# shield_v4.net
KiCad netlist of a schematic drawn in EAGLE
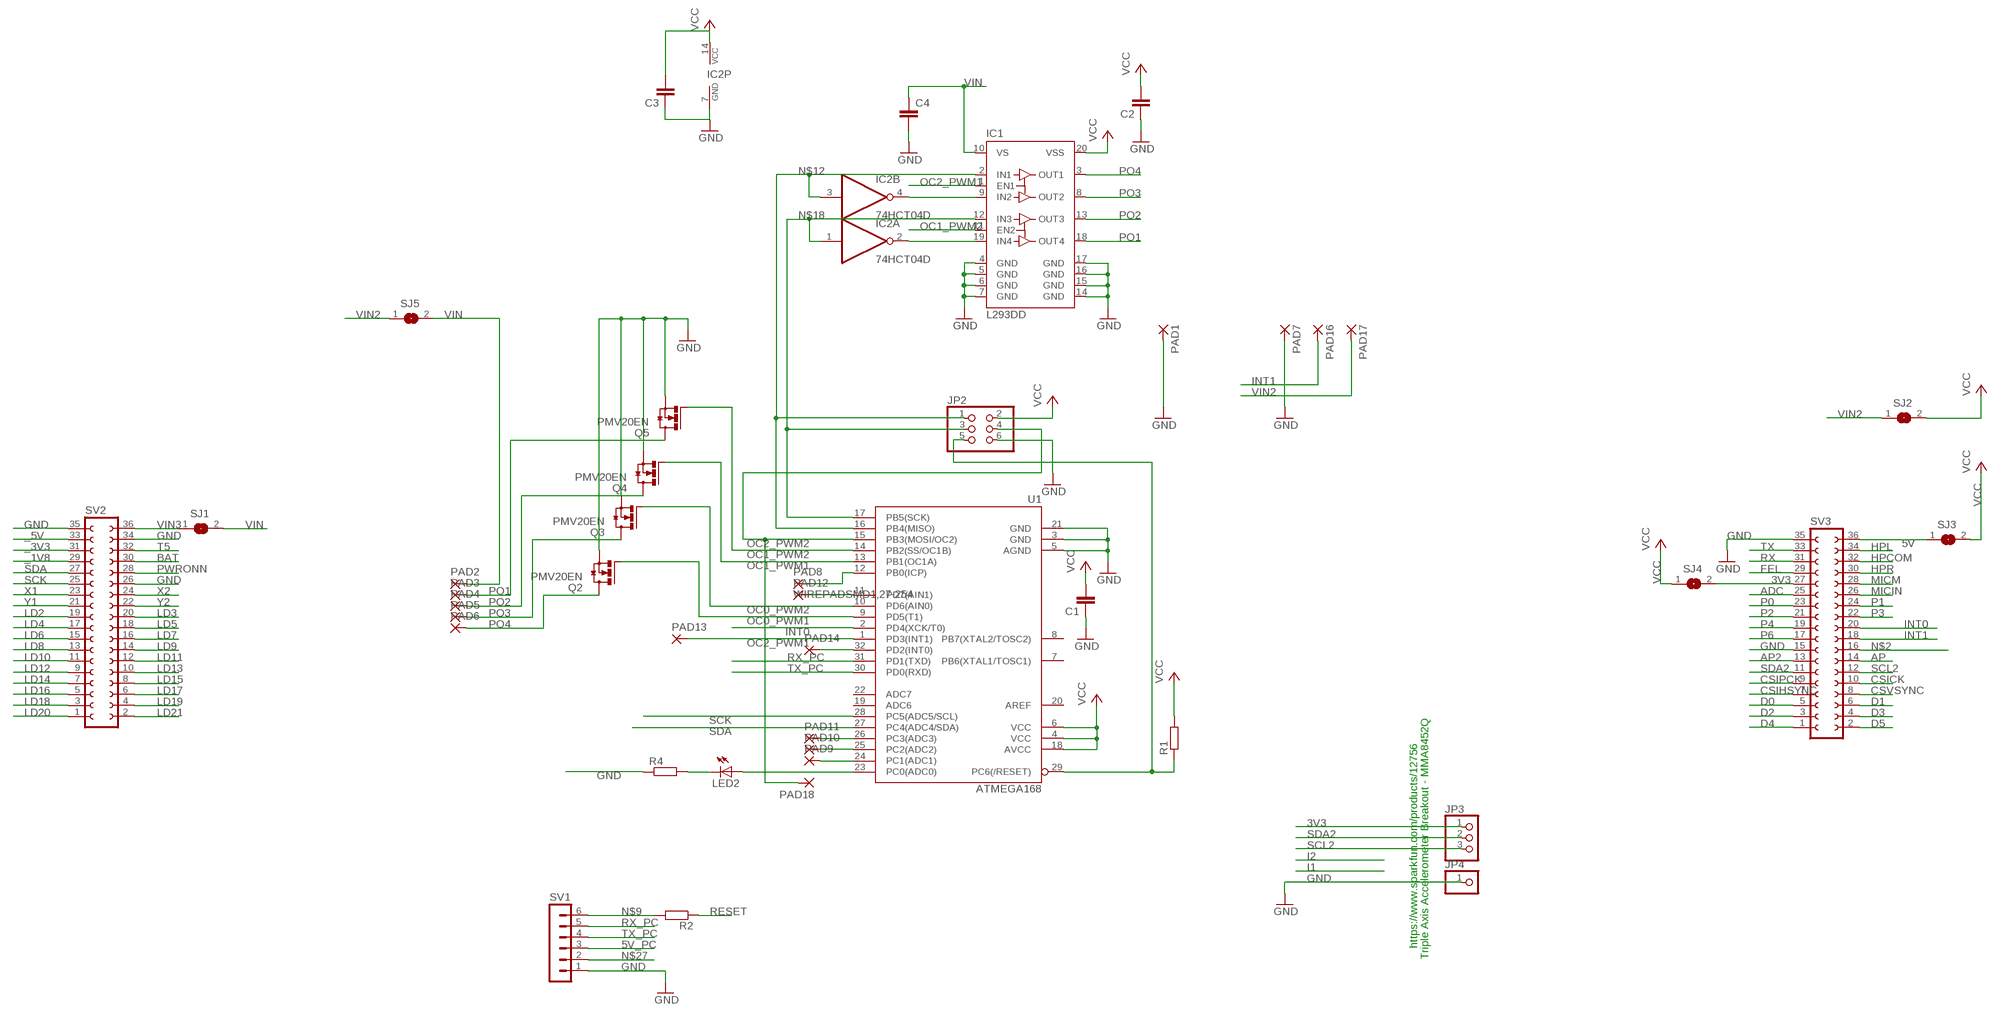
[diagram p0: schematic, sheet 1]

(export (version "E")
  (design (tool "Eeschema 10.0.6"))
  (components
    (comp (ref "C1")
      (value "C-EUC0805")
      (footprint "eagle-import:C0805")
      (libsource (lib "eagle-import") (part "C-EUC0805"))
    )
    (comp (ref "C2")
      (value "C-EUC0805")
      (footprint "eagle-import:C0805")
      (libsource (lib "eagle-import") (part "C-EUC0805"))
    )
    (comp (ref "C3")
      (value "C-EUC0805")
      (footprint "eagle-import:C0805")
      (libsource (lib "eagle-import") (part "C-EUC0805"))
    )
    (comp (ref "C4")
      (value "C-EUC1210")
      (footprint "eagle-import:C1210")
      (libsource (lib "eagle-import") (part "C-EUC1210"))
    )
    (comp (ref "IC1")
      (value "L293DD")
      (footprint "eagle-import:SO20")
      (libsource (lib "eagle-import") (part "L293DD"))
    )
    (comp (ref "IC2")
      (value "74HCT04D")
      (footprint "eagle-import:SO14")
      (libsource (lib "eagle-import") (part "7404DHCT"))
    )
    (comp (ref "JP2")
      (value "PINHD-2X3")
      (footprint "eagle-import:2X03")
      (libsource (lib "eagle-import") (part "PINHD-2X3"))
    )
    (comp (ref "JP3")
      (value "PINHD-1X3")
      (footprint "eagle-import:1X03")
      (libsource (lib "eagle-import") (part "PINHD-1X3"))
    )
    (comp (ref "JP4")
      (value "PINHD-1X1")
      (footprint "eagle-import:1X01")
      (libsource (lib "eagle-import") (part "PINHD-1X1"))
    )
    (comp (ref "LED2")
      (value "LEDCHIP-LED0805")
      (footprint "eagle-import:CHIP-LED0805")
      (libsource (lib "eagle-import") (part "LEDCHIP-LED0805"))
    )
    (comp (ref "PAD1")
      (value "3,17/1,3")
      (footprint "eagle-import:3,17_1,3")
      (libsource (lib "eagle-import") (part "3,17/1,3"))
    )
    (comp (ref "PAD2")
      (value "3,17/1,3")
      (footprint "eagle-import:3,17_1,3")
      (libsource (lib "eagle-import") (part "3,17/1,3"))
    )
    (comp (ref "PAD3")
      (value "3,17/1,3")
      (footprint "eagle-import:3,17_1,3")
      (libsource (lib "eagle-import") (part "3,17/1,3"))
    )
    (comp (ref "PAD4")
      (value "3,17/1,3")
      (footprint "eagle-import:3,17_1,3")
      (libsource (lib "eagle-import") (part "3,17/1,3"))
    )
    (comp (ref "PAD5")
      (value "3,17/1,3")
      (footprint "eagle-import:3,17_1,3")
      (libsource (lib "eagle-import") (part "3,17/1,3"))
    )
    (comp (ref "PAD6")
      (value "3,17/1,3")
      (footprint "eagle-import:3,17_1,3")
      (libsource (lib "eagle-import") (part "3,17/1,3"))
    )
    (comp (ref "PAD7")
      (value "3,17/1,3")
      (footprint "eagle-import:3,17_1,3")
      (libsource (lib "eagle-import") (part "3,17/1,3"))
    )
    (comp (ref "PAD8")
      (value "WIREPADSMD1,27-254")
      (footprint "eagle-import:SMD1,27-2,54")
      (libsource (lib "eagle-import") (part "WIREPADSMD1,27-254"))
    )
    (comp (ref "PAD9")
      (value "3,17/1,3")
      (footprint "eagle-import:3,17_1,3")
      (libsource (lib "eagle-import") (part "3,17/1,3"))
    )
    (comp (ref "PAD10")
      (value "3,17/1,3")
      (footprint "eagle-import:3,17_1,3")
      (libsource (lib "eagle-import") (part "3,17/1,3"))
    )
    (comp (ref "PAD11")
      (value "3,17/1,3")
      (footprint "eagle-import:3,17_1,3")
      (libsource (lib "eagle-import") (part "3,17/1,3"))
    )
    (comp (ref "PAD12")
      (value "SMD2")
      (footprint "eagle-import:SMD1,27-2,54")
      (libsource (lib "eagle-import") (part "SMD2"))
    )
    (comp (ref "PAD13")
      (value "SMD2")
      (footprint "eagle-import:SMD1,27-2,54")
      (libsource (lib "eagle-import") (part "SMD2"))
    )
    (comp (ref "PAD14")
      (value "3,17/1,3")
      (footprint "eagle-import:3,17_1,3")
      (libsource (lib "eagle-import") (part "3,17/1,3"))
    )
    (comp (ref "PAD16")
      (value "3,17/1,3")
      (footprint "eagle-import:3,17_1,3")
      (libsource (lib "eagle-import") (part "3,17/1,3"))
    )
    (comp (ref "PAD17")
      (value "3,17/1,3")
      (footprint "eagle-import:3,17_1,3")
      (libsource (lib "eagle-import") (part "3,17/1,3"))
    )
    (comp (ref "PAD18")
      (value "3,17/1,3")
      (footprint "eagle-import:3,17_1,3")
      (libsource (lib "eagle-import") (part "3,17/1,3"))
    )
    (comp (ref "Q2")
      (value "PMV20EN")
      (footprint "eagle-import:SOT223")
      (libsource (lib "eagle-import") (part "NMOSFET_SMD_223"))
    )
    (comp (ref "Q3")
      (value "PMV20EN")
      (footprint "eagle-import:SOT223")
      (libsource (lib "eagle-import") (part "NMOSFET_SMD_223"))
    )
    (comp (ref "Q4")
      (value "PMV20EN")
      (footprint "eagle-import:SOT223")
      (libsource (lib "eagle-import") (part "NMOSFET_SMD_223"))
    )
    (comp (ref "Q5")
      (value "PMV20EN")
      (footprint "eagle-import:SOT223")
      (libsource (lib "eagle-import") (part "NMOSFET_SMD_223"))
    )
    (comp (ref "R1")
      (value "R-EU_M1206")
      (footprint "eagle-import:M1206")
      (libsource (lib "eagle-import") (part "R-EU_M1206"))
    )
    (comp (ref "R2")
      (value "R-EU_M1206")
      (footprint "eagle-import:M1206")
      (libsource (lib "eagle-import") (part "R-EU_M1206"))
    )
    (comp (ref "R4")
      (value "R-EU_M1206")
      (footprint "eagle-import:M1206")
      (libsource (lib "eagle-import") (part "R-EU_M1206"))
    )
    (comp (ref "SJ1") (value "SJ") (footprint "eagle-import:SJ") (libsource (lib "eagle-import") (part "SJ")))
    (comp (ref "SJ2") (value "SJ") (footprint "eagle-import:SJ") (libsource (lib "eagle-import") (part "SJ")))
    (comp (ref "SJ3") (value "SJ") (footprint "eagle-import:SJ") (libsource (lib "eagle-import") (part "SJ")))
    (comp (ref "SJ4") (value "SJ") (footprint "eagle-import:SJ") (libsource (lib "eagle-import") (part "SJ")))
    (comp (ref "SJ5") (value "SJ") (footprint "eagle-import:SJ") (libsource (lib "eagle-import") (part "SJ")))
    (comp (ref "SV1")
      (value "MA06-1")
      (footprint "eagle-import:MA06-1")
      (libsource (lib "eagle-import") (part "MA06-1"))
    )
    (comp (ref "SV2")
      (value "FE18-2")
      (footprint "eagle-import:FE18-2")
      (libsource (lib "eagle-import") (part "FE18-2"))
    )
    (comp (ref "SV3")
      (value "FE18-2")
      (footprint "eagle-import:FE18-2")
      (libsource (lib "eagle-import") (part "FE18-2"))
    )
    (comp (ref "U1")
      (value "ATMEGA168")
      (footprint "eagle-import:TQFP32-08")
      (libsource (lib "eagle-import") (part "ATMEGA168"))
    )
  )
  (nets
    (net (code "1") (name "/3V3") (class "Default")
      (node (ref "JP3") (pin "1") (pinfunction "1_1") (pintype "passive"))
      (node (ref "SJ4") (pin "2") (pinfunction "2_2") (pintype "passive"))
      (node (ref "SV3") (pin "27") (pinfunction "27_27") (pintype "passive"))
    )
    (net (code "2") (name "/5V") (class "Default")
      (node (ref "SJ3") (pin "1") (pinfunction "1_1") (pintype "passive"))
      (node (ref "SV3") (pin "36") (pinfunction "36_36") (pintype "passive"))
    )
    (net (code "3") (name "/5V_PC") (class "Default")
      (node (ref "SV1") (pin "3") (pinfunction "3_3") (pintype "passive"))
    )
    (net (code "4") (name "/ADC") (class "Default")
      (node (ref "SV3") (pin "25") (pinfunction "25_25") (pintype "passive"))
    )
    (net (code "5") (name "/AP") (class "Default")
      (node (ref "SV3") (pin "14") (pinfunction "14_14") (pintype "passive"))
    )
    (net (code "6") (name "/AP2") (class "Default")
      (node (ref "SV3") (pin "13") (pinfunction "13_13") (pintype "passive"))
    )
    (net (code "7") (name "/BAT") (class "Default")
      (node (ref "SV2") (pin "30") (pinfunction "30_30") (pintype "passive"))
    )
    (net (code "8") (name "/CSICK") (class "Default")
      (node (ref "SV3") (pin "10") (pinfunction "10_10") (pintype "passive"))
    )
    (net (code "9") (name "/CSIHSYNC") (class "Default")
      (node (ref "SV3") (pin "7") (pinfunction "7_7") (pintype "passive"))
    )
    (net (code "10") (name "/CSIPCK") (class "Default")
      (node (ref "SV3") (pin "9") (pinfunction "9_9") (pintype "passive"))
    )
    (net (code "11") (name "/CSVSYNC") (class "Default")
      (node (ref "SV3") (pin "8") (pinfunction "8_8") (pintype "passive"))
    )
    (net (code "12") (name "/D0") (class "Default")
      (node (ref "SV3") (pin "5") (pinfunction "5_5") (pintype "passive"))
    )
    (net (code "13") (name "/D1") (class "Default")
      (node (ref "SV3") (pin "6") (pinfunction "6_6") (pintype "passive"))
    )
    (net (code "14") (name "/D2") (class "Default")
      (node (ref "SV3") (pin "3") (pinfunction "3_3") (pintype "passive"))
    )
    (net (code "15") (name "/D3") (class "Default")
      (node (ref "SV3") (pin "4") (pinfunction "4_4") (pintype "passive"))
    )
    (net (code "16") (name "/D4") (class "Default")
      (node (ref "SV3") (pin "1") (pinfunction "1_1") (pintype "passive"))
    )
    (net (code "17") (name "/D5") (class "Default")
      (node (ref "SV3") (pin "2") (pinfunction "2_2") (pintype "passive"))
    )
    (net (code "18") (name "/FEL") (class "Default")
      (node (ref "SV3") (pin "29") (pinfunction "29_29") (pintype "passive"))
    )
    (net (code "19") (name "/HPCOM") (class "Default")
      (node (ref "SV3") (pin "32") (pinfunction "32_32") (pintype "passive"))
    )
    (net (code "20") (name "/HPL") (class "Default")
      (node (ref "SV3") (pin "34") (pinfunction "34_34") (pintype "passive"))
    )
    (net (code "21") (name "/HPR") (class "Default")
      (node (ref "SV3") (pin "30") (pinfunction "30_30") (pintype "passive"))
    )
    (net (code "24") (name "/INT0") (class "Default")
      (node (ref "SV3") (pin "20") (pinfunction "20_20") (pintype "passive"))
      (node (ref "U1") (pin "2") (pinfunction "PD4(XCK/T0)_2") (pintype "bidirectional"))
    )
    (net (code "25") (name "/INT1") (class "Default")
      (node (ref "PAD16") (pin "1") (pinfunction "P_1") (pintype "passive"))
      (node (ref "SV3") (pin "18") (pinfunction "18_18") (pintype "passive"))
    )
    (net (code "26") (name "/LD2") (class "Default")
      (node (ref "SV2") (pin "19") (pinfunction "19_19") (pintype "passive"))
    )
    (net (code "27") (name "/LD3") (class "Default")
      (node (ref "SV2") (pin "20") (pinfunction "20_20") (pintype "passive"))
    )
    (net (code "28") (name "/LD4") (class "Default")
      (node (ref "SV2") (pin "17") (pinfunction "17_17") (pintype "passive"))
    )
    (net (code "29") (name "/LD5") (class "Default")
      (node (ref "SV2") (pin "18") (pinfunction "18_18") (pintype "passive"))
    )
    (net (code "30") (name "/LD6") (class "Default")
      (node (ref "SV2") (pin "15") (pinfunction "15_15") (pintype "passive"))
    )
    (net (code "31") (name "/LD7") (class "Default")
      (node (ref "SV2") (pin "16") (pinfunction "16_16") (pintype "passive"))
    )
    (net (code "32") (name "/LD8") (class "Default")
      (node (ref "SV2") (pin "13") (pinfunction "13_13") (pintype "passive"))
    )
    (net (code "33") (name "/LD9") (class "Default")
      (node (ref "SV2") (pin "14") (pinfunction "14_14") (pintype "passive"))
    )
    (net (code "34") (name "/LD10") (class "Default")
      (node (ref "SV2") (pin "11") (pinfunction "11_11") (pintype "passive"))
    )
    (net (code "35") (name "/LD11") (class "Default")
      (node (ref "SV2") (pin "12") (pinfunction "12_12") (pintype "passive"))
    )
    (net (code "36") (name "/LD12") (class "Default")
      (node (ref "SV2") (pin "9") (pinfunction "9_9") (pintype "passive"))
    )
    (net (code "37") (name "/LD13") (class "Default")
      (node (ref "SV2") (pin "10") (pinfunction "10_10") (pintype "passive"))
    )
    (net (code "38") (name "/LD14") (class "Default")
      (node (ref "SV2") (pin "7") (pinfunction "7_7") (pintype "passive"))
    )
    (net (code "39") (name "/LD15") (class "Default")
      (node (ref "SV2") (pin "8") (pinfunction "8_8") (pintype "passive"))
    )
    (net (code "40") (name "/LD16") (class "Default")
      (node (ref "SV2") (pin "5") (pinfunction "5_5") (pintype "passive"))
    )
    (net (code "41") (name "/LD17") (class "Default")
      (node (ref "SV2") (pin "6") (pinfunction "6_6") (pintype "passive"))
    )
    (net (code "42") (name "/LD18") (class "Default")
      (node (ref "SV2") (pin "3") (pinfunction "3_3") (pintype "passive"))
    )
    (net (code "43") (name "/LD19") (class "Default")
      (node (ref "SV2") (pin "4") (pinfunction "4_4") (pintype "passive"))
    )
    (net (code "44") (name "/LD20") (class "Default")
      (node (ref "SV2") (pin "1") (pinfunction "1_1") (pintype "passive"))
    )
    (net (code "45") (name "/LD21") (class "Default")
      (node (ref "SV2") (pin "2") (pinfunction "2_2") (pintype "passive"))
    )
    (net (code "46") (name "/MICIN") (class "Default")
      (node (ref "SV3") (pin "26") (pinfunction "26_26") (pintype "passive"))
    )
    (net (code "47") (name "/MICM") (class "Default")
      (node (ref "SV3") (pin "28") (pinfunction "28_28") (pintype "passive"))
    )
    (net (code "48") (name "/N$2") (class "Default")
      (node (ref "SV3") (pin "16") (pinfunction "16_16") (pintype "passive"))
    )
    (net (code "49") (name "/N$9") (class "Default")
      (node (ref "R2") (pin "2") (pinfunction "2_2") (pintype "passive"))
      (node (ref "SV1") (pin "6") (pinfunction "6_6") (pintype "passive"))
    )
    (net (code "50") (name "/N$12") (class "Default")
      (node (ref "IC1") (pin "2") (pinfunction "IN1_2") (pintype "input"))
      (node (ref "IC2") (pin "3") (pinfunction "I_3") (pintype "input"))
      (node (ref "JP2") (pin "1") (pinfunction "1_1") (pintype "passive"))
      (node (ref "U1") (pin "16") (pinfunction "PB4(MISO)_16") (pintype "bidirectional"))
    )
    (net (code "51") (name "/N$18") (class "Default")
      (node (ref "IC1") (pin "12") (pinfunction "IN3_12") (pintype "input"))
      (node (ref "IC2") (pin "1") (pinfunction "I_1") (pintype "input"))
      (node (ref "JP2") (pin "3") (pinfunction "3_3") (pintype "passive"))
      (node (ref "U1") (pin "17") (pinfunction "PB5(SCK)_17") (pintype "bidirectional"))
    )
    (net (code "52") (name "/N$27") (class "Default")
      (node (ref "SV1") (pin "2") (pinfunction "2_2") (pintype "passive"))
    )
    (net (code "53") (name "/OC0_PWM1") (class "Default")
      (node (ref "Q2") (pin "1") (pinfunction "G_1") (pintype "passive"))
      (node (ref "U1") (pin "9") (pinfunction "PD5(T1)_9") (pintype "bidirectional"))
    )
    (net (code "54") (name "/OC0_PWM2") (class "Default")
      (node (ref "Q3") (pin "1") (pinfunction "G_1") (pintype "passive"))
      (node (ref "U1") (pin "10") (pinfunction "PD6(AIN0)_10") (pintype "bidirectional"))
    )
    (net (code "55") (name "/OC1_PWM1") (class "Default")
      (node (ref "Q4") (pin "1") (pinfunction "G_1") (pintype "passive"))
      (node (ref "U1") (pin "13") (pinfunction "PB1(OC1A)_13") (pintype "bidirectional"))
    )
    (net (code "56") (name "/OC1_PWM2") (class "Default")
      (node (ref "IC1") (pin "11") (pinfunction "EN2_11") (pintype "input"))
      (node (ref "Q5") (pin "1") (pinfunction "G_1") (pintype "passive"))
      (node (ref "U1") (pin "14") (pinfunction "PB2(SS/OC1B)_14") (pintype "bidirectional"))
    )
    (net (code "57") (name "/OC2_PWM1") (class "Default")
      (node (ref "IC1") (pin "1") (pinfunction "EN1_1") (pintype "input"))
      (node (ref "PAD13") (pin "1") (pinfunction "P_1") (pintype "passive"))
      (node (ref "U1") (pin "1") (pinfunction "PD3(INT1)_1") (pintype "bidirectional"))
    )
    (net (code "58") (name "/OC2_PWM2") (class "Default")
      (node (ref "JP2") (pin "4") (pinfunction "4_4") (pintype "passive"))
      (node (ref "PAD18") (pin "1") (pinfunction "P_1") (pintype "passive"))
      (node (ref "U1") (pin "15") (pinfunction "PB3(MOSI/OC2)_15") (pintype "bidirectional"))
    )
    (net (code "59") (name "/P0") (class "Default")
      (node (ref "SV3") (pin "23") (pinfunction "23_23") (pintype "passive"))
    )
    (net (code "60") (name "/P1") (class "Default")
      (node (ref "SV3") (pin "24") (pinfunction "24_24") (pintype "passive"))
    )
    (net (code "61") (name "/P2") (class "Default")
      (node (ref "SV3") (pin "21") (pinfunction "21_21") (pintype "passive"))
    )
    (net (code "62") (name "/P3") (class "Default")
      (node (ref "SV3") (pin "22") (pinfunction "22_22") (pintype "passive"))
    )
    (net (code "63") (name "/P4") (class "Default")
      (node (ref "SV3") (pin "19") (pinfunction "19_19") (pintype "passive"))
    )
    (net (code "64") (name "/P6") (class "Default")
      (node (ref "SV3") (pin "17") (pinfunction "17_17") (pintype "passive"))
    )
    (net (code "65") (name "/PO1") (class "Default")
      (node (ref "IC1") (pin "18") (pinfunction "OUT4_18") (pintype "output"))
      (node (ref "PAD3") (pin "1") (pinfunction "P_1") (pintype "passive"))
      (node (ref "Q5") (pin "2") (pinfunction "D_2") (pintype "passive"))
      (node (ref "Q5") (pin "4") (pinfunction "D_4") (pintype "passive"))
    )
    (net (code "66") (name "/PO2") (class "Default")
      (node (ref "IC1") (pin "13") (pinfunction "OUT3_13") (pintype "output"))
      (node (ref "PAD4") (pin "1") (pinfunction "P_1") (pintype "passive"))
      (node (ref "Q4") (pin "2") (pinfunction "D_2") (pintype "passive"))
      (node (ref "Q4") (pin "4") (pinfunction "D_4") (pintype "passive"))
    )
    (net (code "67") (name "/PO3") (class "Default")
      (node (ref "IC1") (pin "8") (pinfunction "OUT2_8") (pintype "output"))
      (node (ref "PAD5") (pin "1") (pinfunction "P_1") (pintype "passive"))
      (node (ref "Q3") (pin "2") (pinfunction "D_2") (pintype "passive"))
      (node (ref "Q3") (pin "4") (pinfunction "D_4") (pintype "passive"))
    )
    (net (code "68") (name "/PO4") (class "Default")
      (node (ref "IC1") (pin "3") (pinfunction "OUT1_3") (pintype "output"))
      (node (ref "PAD6") (pin "1") (pinfunction "P_1") (pintype "passive"))
      (node (ref "Q2") (pin "2") (pinfunction "D_2") (pintype "passive"))
      (node (ref "Q2") (pin "4") (pinfunction "D_4") (pintype "passive"))
    )
    (net (code "69") (name "/PWRONN") (class "Default")
      (node (ref "SV2") (pin "28") (pinfunction "28_28") (pintype "passive"))
    )
    (net (code "70") (name "/RESET") (class "Default")
      (node (ref "JP2") (pin "5") (pinfunction "5_5") (pintype "passive"))
      (node (ref "R1") (pin "1") (pinfunction "1_1") (pintype "passive"))
      (node (ref "R2") (pin "1") (pinfunction "1_1") (pintype "passive"))
      (node (ref "U1") (pin "29") (pinfunction "PC6(/RESET)_29") (pintype "bidirectional"))
    )
    (net (code "71") (name "/RX") (class "Default")
      (node (ref "SV3") (pin "31") (pinfunction "31_31") (pintype "passive"))
    )
    (net (code "72") (name "/RX_PC") (class "Default")
      (node (ref "SV1") (pin "5") (pinfunction "5_5") (pintype "passive"))
      (node (ref "U1") (pin "31") (pinfunction "PD1(TXD)_31") (pintype "bidirectional"))
    )
    (net (code "73") (name "/SCK") (class "Default")
      (node (ref "SV2") (pin "25") (pinfunction "25_25") (pintype "passive"))
      (node (ref "U1") (pin "28") (pinfunction "PC5(ADC5/SCL)_28") (pintype "bidirectional"))
    )
    (net (code "74") (name "/SCL2") (class "Default")
      (node (ref "JP3") (pin "3") (pinfunction "3_3") (pintype "passive"))
      (node (ref "SV3") (pin "12") (pinfunction "12_12") (pintype "passive"))
    )
    (net (code "75") (name "/SDA") (class "Default")
      (node (ref "SV2") (pin "27") (pinfunction "27_27") (pintype "passive"))
      (node (ref "U1") (pin "27") (pinfunction "PC4(ADC4/SDA)_27") (pintype "bidirectional"))
    )
    (net (code "76") (name "/SDA2") (class "Default")
      (node (ref "JP3") (pin "2") (pinfunction "2_2") (pintype "passive"))
      (node (ref "SV3") (pin "11") (pinfunction "11_11") (pintype "passive"))
    )
    (net (code "77") (name "/T5") (class "Default")
      (node (ref "SV2") (pin "32") (pinfunction "32_32") (pintype "passive"))
    )
    (net (code "78") (name "/TX") (class "Default")
      (node (ref "SV3") (pin "33") (pinfunction "33_33") (pintype "passive"))
    )
    (net (code "79") (name "/TX_PC") (class "Default")
      (node (ref "SV1") (pin "4") (pinfunction "4_4") (pintype "passive"))
      (node (ref "U1") (pin "30") (pinfunction "PD0(RXD)_30") (pintype "bidirectional"))
    )
    (net (code "80") (name "/VIN") (class "Default")
      (node (ref "C4") (pin "1") (pinfunction "1_1") (pintype "passive"))
      (node (ref "IC1") (pin "10") (pinfunction "VS_10") (pintype "power_in"))
      (node (ref "PAD2") (pin "1") (pinfunction "P_1") (pintype "passive"))
      (node (ref "SJ1") (pin "2") (pinfunction "2_2") (pintype "passive"))
      (node (ref "SJ5") (pin "2") (pinfunction "2_2") (pintype "passive"))
    )
    (net (code "81") (name "/VIN2") (class "Default")
      (node (ref "PAD17") (pin "1") (pinfunction "P_1") (pintype "passive"))
      (node (ref "SJ2") (pin "1") (pinfunction "1_1") (pintype "passive"))
      (node (ref "SJ5") (pin "1") (pinfunction "1_1") (pintype "passive"))
    )
    (net (code "82") (name "/VIN3") (class "Default")
      (node (ref "SJ1") (pin "1") (pinfunction "1_1") (pintype "passive"))
      (node (ref "SV2") (pin "36") (pinfunction "36_36") (pintype "passive"))
    )
    (net (code "83") (name "/X1") (class "Default")
      (node (ref "SV2") (pin "23") (pinfunction "23_23") (pintype "passive"))
    )
    (net (code "84") (name "/X2") (class "Default")
      (node (ref "SV2") (pin "24") (pinfunction "24_24") (pintype "passive"))
    )
    (net (code "85") (name "/Y1") (class "Default")
      (node (ref "SV2") (pin "21") (pinfunction "21_21") (pintype "passive"))
    )
    (net (code "86") (name "/Y2") (class "Default")
      (node (ref "SV2") (pin "22") (pinfunction "22_22") (pintype "passive"))
    )
    (net (code "87") (name "/_1V8") (class "Default")
      (node (ref "SV2") (pin "29") (pinfunction "29_29") (pintype "passive"))
    )
    (net (code "88") (name "/_3V3") (class "Default")
      (node (ref "SV2") (pin "31") (pinfunction "31_31") (pintype "passive"))
    )
    (net (code "89") (name "/_5V") (class "Default")
      (node (ref "SV2") (pin "33") (pinfunction "33_33") (pintype "passive"))
    )
    (net (code "90") (name "GND") (class "Default")
      (node (ref "C1") (pin "1") (pinfunction "1_1") (pintype "passive"))
      (node (ref "C2") (pin "1") (pinfunction "1_1") (pintype "passive"))
      (node (ref "C3") (pin "1") (pinfunction "1_1") (pintype "passive"))
      (node (ref "C4") (pin "2") (pinfunction "2_2") (pintype "passive"))
      (node (ref "IC1") (pin "14") (pinfunction "GND_14") (pintype "power_in"))
      (node (ref "IC1") (pin "15") (pinfunction "GND_15") (pintype "power_in"))
      (node (ref "IC1") (pin "16") (pinfunction "GND_16") (pintype "power_in"))
      (node (ref "IC1") (pin "17") (pinfunction "GND_17") (pintype "power_in"))
      (node (ref "IC1") (pin "4") (pinfunction "GND_4") (pintype "power_in"))
      (node (ref "IC1") (pin "5") (pinfunction "GND_5") (pintype "power_in"))
      (node (ref "IC1") (pin "6") (pinfunction "GND_6") (pintype "power_in"))
      (node (ref "IC1") (pin "7") (pinfunction "GND_7") (pintype "power_in"))
      (node (ref "IC2") (pin "7") (pinfunction "GND_7") (pintype "power_in"))
      (node (ref "JP2") (pin "6") (pinfunction "6_6") (pintype "passive"))
      (node (ref "JP4") (pin "1") (pinfunction "1_1") (pintype "passive"))
      (node (ref "PAD1") (pin "1") (pinfunction "P_1") (pintype "passive"))
      (node (ref "PAD7") (pin "1") (pinfunction "P_1") (pintype "passive"))
      (node (ref "Q2") (pin "3") (pinfunction "S_3") (pintype "passive"))
      (node (ref "Q3") (pin "3") (pinfunction "S_3") (pintype "passive"))
      (node (ref "Q4") (pin "3") (pinfunction "S_3") (pintype "passive"))
      (node (ref "Q5") (pin "3") (pinfunction "S_3") (pintype "passive"))
      (node (ref "R4") (pin "1") (pinfunction "1_1") (pintype "passive"))
      (node (ref "SV1") (pin "1") (pinfunction "1_1") (pintype "passive"))
      (node (ref "SV2") (pin "26") (pinfunction "26_26") (pintype "passive"))
      (node (ref "SV2") (pin "34") (pinfunction "34_34") (pintype "passive"))
      (node (ref "SV2") (pin "35") (pinfunction "35_35") (pintype "passive"))
      (node (ref "SV3") (pin "15") (pinfunction "15_15") (pintype "passive"))
      (node (ref "SV3") (pin "35") (pinfunction "35_35") (pintype "passive"))
      (node (ref "U1") (pin "21") (pinfunction "GND_21") (pintype "bidirectional"))
      (node (ref "U1") (pin "3") (pinfunction "GND_3") (pintype "bidirectional"))
      (node (ref "U1") (pin "5") (pinfunction "AGND_5") (pintype "bidirectional"))
    )
    (net (code "91") (name "Net-(IC1-IN2)") (class "Default")
      (node (ref "IC1") (pin "9") (pinfunction "IN2_9") (pintype "input"))
      (node (ref "IC2") (pin "4") (pinfunction "O_4") (pintype "output"))
    )
    (net (code "92") (name "Net-(IC1-IN4)") (class "Default")
      (node (ref "IC1") (pin "19") (pinfunction "IN4_19") (pintype "input"))
      (node (ref "IC2") (pin "2") (pinfunction "O_2") (pintype "output"))
    )
    (net (code "93") (name "Net-(LED2-PadC)") (class "Default")
      (node (ref "LED2") (pin "C") (pinfunction "C_C") (pintype "passive"))
      (node (ref "R4") (pin "2") (pinfunction "2_2") (pintype "passive"))
    )
    (net (code "94") (name "Net-(PAD8-P)") (class "Default")
      (node (ref "PAD8") (pin "1") (pinfunction "P_1") (pintype "passive"))
      (node (ref "U1") (pin "12") (pinfunction "PB0(ICP)_12") (pintype "bidirectional"))
    )
    (net (code "95") (name "Net-(PAD9-P)") (class "Default")
      (node (ref "PAD9") (pin "1") (pinfunction "P_1") (pintype "passive"))
      (node (ref "U1") (pin "24") (pinfunction "PC1(ADC1)_24") (pintype "bidirectional"))
    )
    (net (code "96") (name "Net-(PAD10-P)") (class "Default")
      (node (ref "PAD10") (pin "1") (pinfunction "P_1") (pintype "passive"))
      (node (ref "U1") (pin "25") (pinfunction "PC2(ADC2)_25") (pintype "bidirectional"))
    )
    (net (code "97") (name "Net-(PAD11-P)") (class "Default")
      (node (ref "PAD11") (pin "1") (pinfunction "P_1") (pintype "passive"))
      (node (ref "U1") (pin "26") (pinfunction "PC3(ADC3)_26") (pintype "bidirectional"))
    )
    (net (code "98") (name "Net-(PAD12-P)") (class "Default")
      (node (ref "PAD12") (pin "1") (pinfunction "P_1") (pintype "passive"))
      (node (ref "U1") (pin "11") (pinfunction "PD7(AIN1)_11") (pintype "bidirectional"))
    )
    (net (code "99") (name "Net-(PAD14-P)") (class "Default")
      (node (ref "PAD14") (pin "1") (pinfunction "P_1") (pintype "passive"))
      (node (ref "U1") (pin "32") (pinfunction "PD2(INT0)_32") (pintype "bidirectional"))
    )
    (net (code "100") (name "Net-(U1-PC0(ADC0))") (class "Default")
      (node (ref "LED2") (pin "A") (pinfunction "A_A") (pintype "passive"))
      (node (ref "U1") (pin "23") (pinfunction "PC0(ADC0)_23") (pintype "bidirectional"))
    )
    (net (code "101") (name "VCC") (class "Default")
      (node (ref "C1") (pin "2") (pinfunction "2_2") (pintype "passive"))
      (node (ref "C2") (pin "2") (pinfunction "2_2") (pintype "passive"))
      (node (ref "C3") (pin "2") (pinfunction "2_2") (pintype "passive"))
      (node (ref "IC1") (pin "20") (pinfunction "VSS_20") (pintype "power_in"))
      (node (ref "IC2") (pin "14") (pinfunction "VCC_14") (pintype "power_in"))
      (node (ref "JP2") (pin "2") (pinfunction "2_2") (pintype "passive"))
      (node (ref "R1") (pin "2") (pinfunction "2_2") (pintype "passive"))
      (node (ref "SJ2") (pin "2") (pinfunction "2_2") (pintype "passive"))
      (node (ref "SJ3") (pin "2") (pinfunction "2_2") (pintype "passive"))
      (node (ref "SJ4") (pin "1") (pinfunction "1_1") (pintype "passive"))
      (node (ref "U1") (pin "18") (pinfunction "AVCC_18") (pintype "bidirectional"))
      (node (ref "U1") (pin "4") (pinfunction "VCC_4") (pintype "bidirectional"))
      (node (ref "U1") (pin "6") (pinfunction "VCC_6") (pintype "bidirectional"))
    )
    (net (code "102") (name "unconnected-(U1-ADC6-Pad19)") (class "Default")
      (node (ref "U1") (pin "19") (pinfunction "ADC6_19") (pintype "bidirectional"))
    )
    (net (code "103") (name "unconnected-(U1-ADC7-Pad22)") (class "Default")
      (node (ref "U1") (pin "22") (pinfunction "ADC7_22") (pintype "bidirectional"))
    )
    (net (code "104") (name "unconnected-(U1-AREF-Pad20)") (class "Default")
      (node (ref "U1") (pin "20") (pinfunction "AREF_20") (pintype "bidirectional"))
    )
    (net (code "105") (name "unconnected-(U1-PB6(XTAL1{slash}TOSC1)-Pad7)") (class "Default")
      (node (ref "U1") (pin "7") (pinfunction "PB6(XTAL1/TOSC1)_7") (pintype "bidirectional"))
    )
    (net (code "106") (name "unconnected-(U1-PB7(XTAL2{slash}TOSC2)-Pad8)") (class "Default")
      (node (ref "U1") (pin "8") (pinfunction "PB7(XTAL2/TOSC2)_8") (pintype "bidirectional"))
    )
  )
)
